# Industrial-Controller_Temperature.net
KiCad netlist of a schematic drawn in Altium Designer
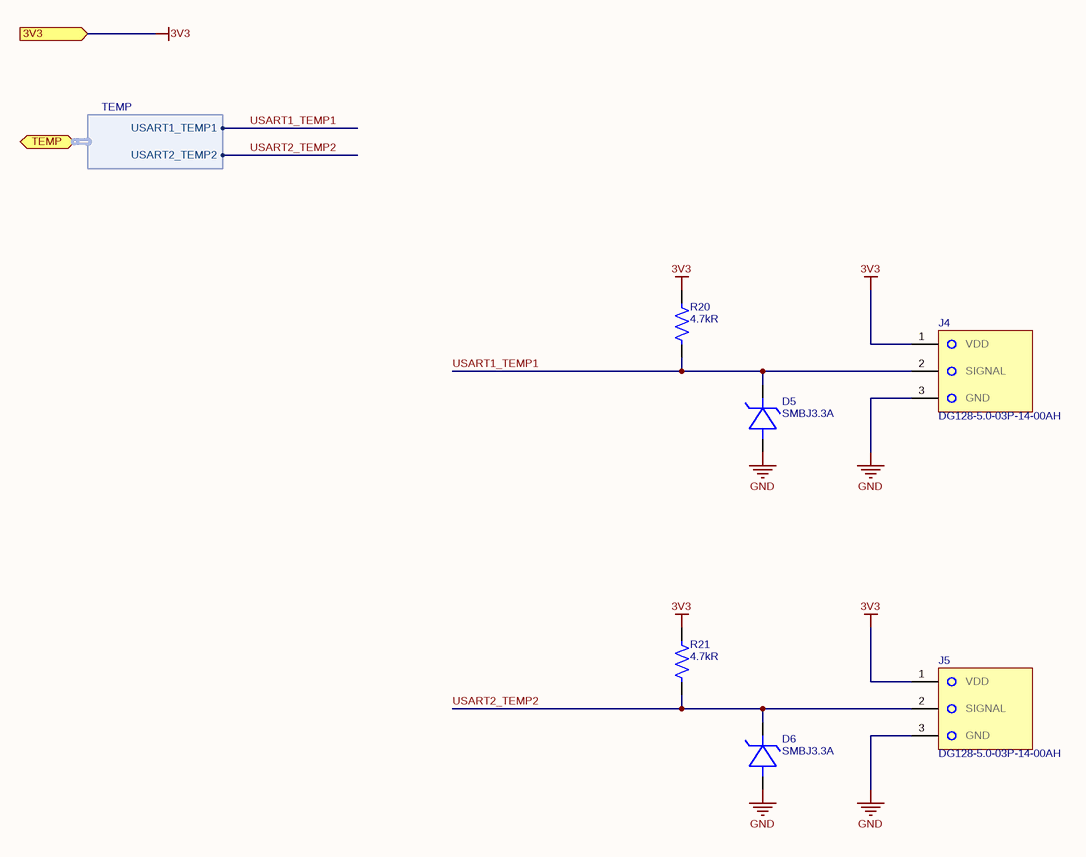
[diagram p0: Industrial-Controller_Temperature.SchDoc]

(export (version "E")
  (design (tool "Eeschema 10.0.6"))
  (components
    (comp (ref "D5")
      (value "SMBJ3.3A")
      (footprint "SMB")
      (description "TVS DIODE 3.3VWM 4.1VC SMB")
      (libsource (lib "Industrial-Controller") (part "SMBJ3.3A"))
    )
    (comp (ref "D6")
      (value "SMBJ3.3A")
      (footprint "SMB")
      (description "TVS DIODE 3.3VWM 4.1VC SMB")
      (libsource (lib "Industrial-Controller") (part "SMBJ3.3A"))
    )
    (comp (ref "J4")
      (value "DG128-5.0-03P-14-00AH")
      (footprint "DG128-5.0-03P-14")
      (description "TERM BLK 3P TOP ENTRY 5MM SMD")
      (libsource (lib "Industrial-Controller") (part "DG128-5.0-03P-14"))
    )
    (comp (ref "J5")
      (value "DG128-5.0-03P-14-00AH")
      (footprint "DG128-5.0-03P-14")
      (description "TERM BLK 3P TOP ENTRY 5MM SMD")
      (libsource (lib "Industrial-Controller") (part "DG128-5.0-03P-14"))
    )
    (comp (ref "R20")
      (value "4.7kR")
      (footprint "RES_0603")
      (description "RES 4.7K OHM 1% 1/10W 0603")
      (fields (field (name "TOLERANCE") "1%"))
      (libsource (lib "Industrial-Controller") (part "RC0603FR-074K7L"))
    )
    (comp (ref "R21")
      (value "4.7kR")
      (footprint "RES_0603")
      (description "RES 4.7K OHM 1% 1/10W 0603")
      (fields (field (name "TOLERANCE") "1%"))
      (libsource (lib "Industrial-Controller") (part "RC0603FR-074K7L"))
    )
  )
  (nets
    (net (code "2") (name "/USART1_TEMP1") (class "Default")
      (node (ref "D5") (pin "1") (pinfunction "C_1") (pintype "passive"))
      (node (ref "J4") (pin "2") (pinfunction "2_2") (pintype "passive"))
      (node (ref "R20") (pin "2") (pinfunction "2_2") (pintype "passive"))
    )
    (net (code "3") (name "/USART2_TEMP2") (class "Default")
      (node (ref "D6") (pin "1") (pinfunction "C_1") (pintype "passive"))
      (node (ref "J5") (pin "2") (pinfunction "2_2") (pintype "passive"))
      (node (ref "R21") (pin "2") (pinfunction "2_2") (pintype "passive"))
    )
    (net (code "5") (name "3V3") (class "Default")
      (node (ref "J4") (pin "1") (pinfunction "1_1") (pintype "passive"))
      (node (ref "J5") (pin "1") (pinfunction "1_1") (pintype "passive"))
      (node (ref "R20") (pin "1") (pinfunction "1_1") (pintype "passive"))
      (node (ref "R21") (pin "1") (pinfunction "1_1") (pintype "passive"))
    )
    (net (code "6") (name "GND") (class "Default")
      (node (ref "D5") (pin "2") (pinfunction "A_2") (pintype "passive"))
      (node (ref "D6") (pin "2") (pinfunction "A_2") (pintype "passive"))
      (node (ref "J4") (pin "3") (pinfunction "3_3") (pintype "passive"))
      (node (ref "J5") (pin "3") (pinfunction "3_3") (pintype "passive"))
    )
  )
)
